# 9_-RELAYS.net
KiCad netlist of a schematic drawn in Altium Designer
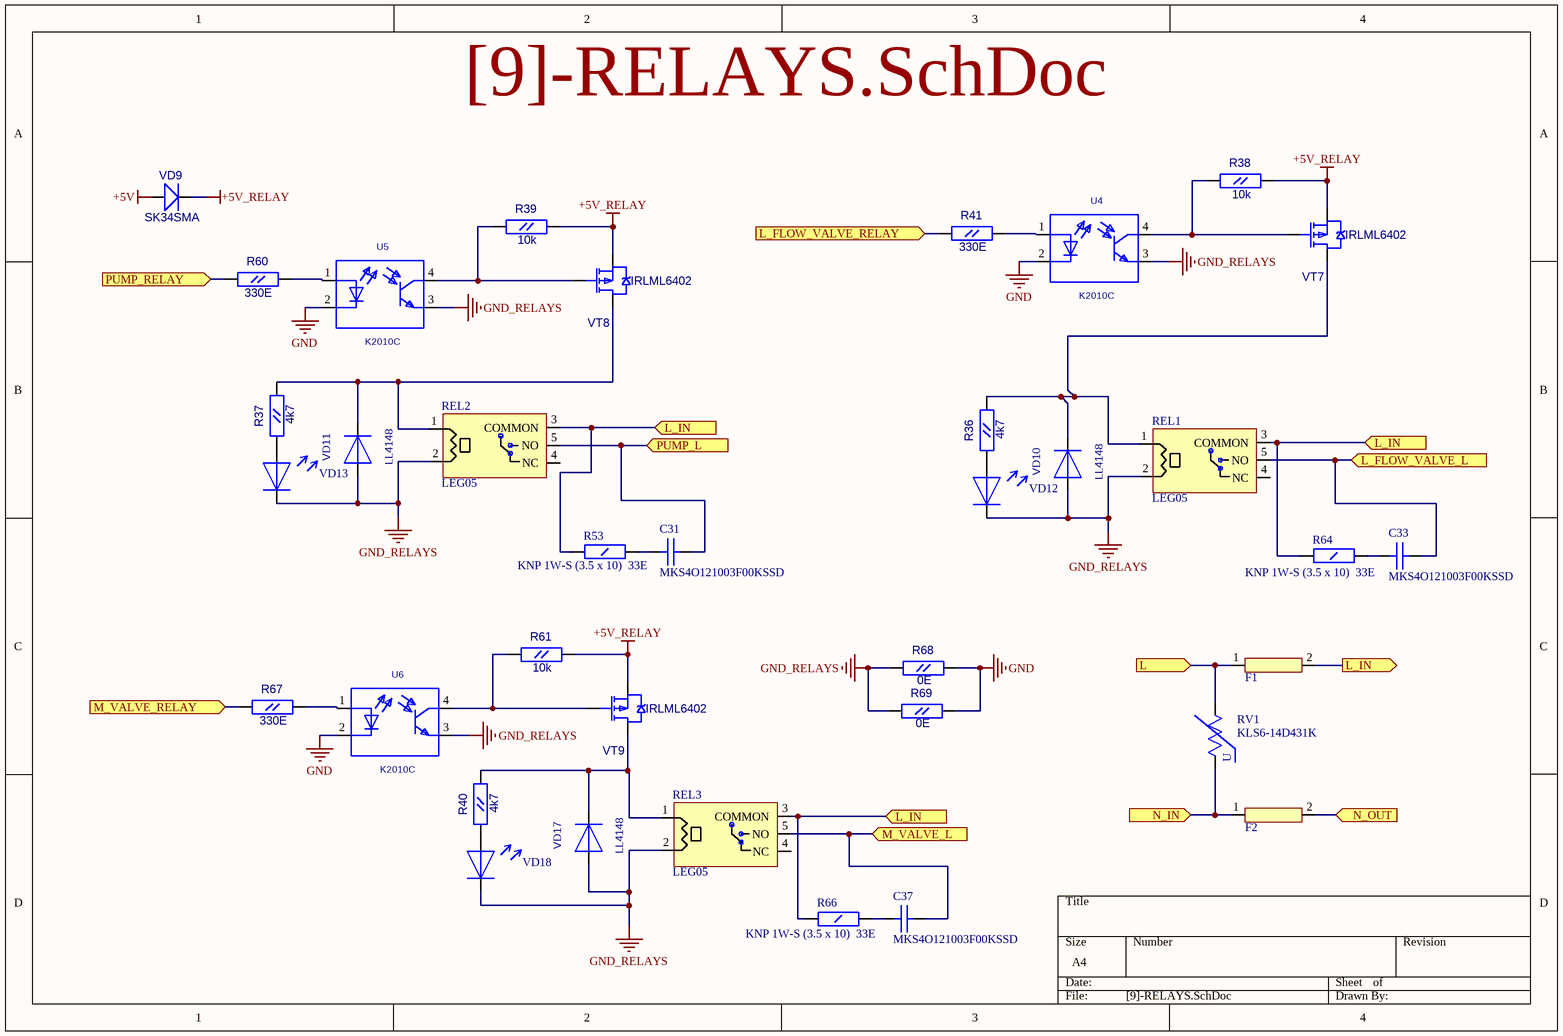
[diagram p0: [9]-RELAYS.SchDoc]

(export (version "E")
  (design (tool "Eeschema 10.0.6"))
  (components
    (comp (ref "C31")
      (value "MKS4O121003F00KSSD")
      (footprint "CAP_HV_13x5")
      (libsource (lib "fizik_lib") (part "CAP_HV_13x5"))
    )
    (comp (ref "C33")
      (value "MKS4O121003F00KSSD")
      (footprint "CAP_HV_13x5")
      (libsource (lib "fizik_lib") (part "CAP_HV_13x5"))
    )
    (comp (ref "C37")
      (value "MKS4O121003F00KSSD")
      (footprint "CAP_HV_13x5")
      (libsource (lib "fizik_lib") (part "CAP_HV_13x5"))
    )
    (comp (ref "F1")
      (value "KLS5-266(5x20)")
      (footprint "Fuse_5x20")
      (libsource (lib "fizik_lib") (part "Fuse KLS5-266(5x20)"))
    )
    (comp (ref "F2")
      (value "KLS5-266(5x20)")
      (footprint "Fuse_5x20")
      (libsource (lib "fizik_lib") (part "Fuse KLS5-266(5x20)"))
    )
    (comp (ref "R36")
      (value "4k7")
      (footprint "RC0603")
      (description "RC0603")
      (libsource (lib "fizik_lib") (part "RC0603"))
    )
    (comp (ref "R37")
      (value "4k7")
      (footprint "RC0603")
      (description "RC0603")
      (libsource (lib "fizik_lib") (part "RC0603"))
    )
    (comp (ref "R38")
      (value "10k")
      (footprint "RC0603")
      (description "RC0603")
      (libsource (lib "fizik_lib") (part "RC0603"))
    )
    (comp (ref "R39")
      (value "10k")
      (footprint "RC0603")
      (description "RC0603")
      (libsource (lib "fizik_lib") (part "RC0603"))
    )
    (comp (ref "R40")
      (value "4k7")
      (footprint "RC0603")
      (description "RC0603")
      (libsource (lib "fizik_lib") (part "RC0603"))
    )
    (comp (ref "R41")
      (value "330E")
      (footprint "RC0603")
      (description "RC0603")
      (libsource (lib "fizik_lib") (part "RC0603"))
    )
    (comp (ref "R53")
      (value "KNP 1W-S (3.5 x 10)  33E")
      (footprint "RES_10x4_THD")
      (description "THR resisto r10x3mm 0.5W")
      (libsource (lib "fizik_lib") (part "RC_1003_THR"))
    )
    (comp (ref "R60")
      (value "330E")
      (footprint "RC0603")
      (description "RC0603")
      (libsource (lib "fizik_lib") (part "RC0603"))
    )
    (comp (ref "R61")
      (value "10k")
      (footprint "RC0603")
      (description "RC0603")
      (libsource (lib "fizik_lib") (part "RC0603"))
    )
    (comp (ref "R64")
      (value "KNP 1W-S (3.5 x 10)  33E")
      (footprint "RES_10x4_THD")
      (description "THR resisto r10x3mm 0.5W")
      (libsource (lib "fizik_lib") (part "RC_1003_THR"))
    )
    (comp (ref "R66")
      (value "KNP 1W-S (3.5 x 10)  33E")
      (footprint "RES_10x4_THD")
      (description "THR resisto r10x3mm 0.5W")
      (libsource (lib "fizik_lib") (part "RC_1003_THR"))
    )
    (comp (ref "R67")
      (value "330E")
      (footprint "RC0603")
      (description "RC0603")
      (libsource (lib "fizik_lib") (part "RC0603"))
    )
    (comp (ref "R68")
      (value "0E")
      (footprint "RC0805")
      (description "RC0805")
      (libsource (lib "fizik_lib") (part "RC0805"))
    )
    (comp (ref "R69")
      (value "0E")
      (footprint "RC0805")
      (description "RC0805")
      (libsource (lib "fizik_lib") (part "RC0805"))
    )
    (comp (ref "REL1")
      (value "LEG05")
      (footprint "RELAY_SRD-05")
      (description "Relay 5V 70mA Songle")
      (libsource (lib "fizik_lib") (part "SRD-05VDC-SL-C"))
    )
    (comp (ref "REL2")
      (value "LEG05")
      (footprint "RELAY_SRD-05")
      (description "Relay 5V 70mA Songle")
      (libsource (lib "fizik_lib") (part "SRD-05VDC-SL-C"))
    )
    (comp (ref "REL3")
      (value "LEG05")
      (footprint "RELAY_SRD-05")
      (description "Relay 5V 70mA Songle")
      (libsource (lib "fizik_lib") (part "SRD-05VDC-SL-C"))
    )
    (comp (ref "RV1")
      (value "KLS6-14D431K")
      (footprint "Varistor_14MM")
      (description "Varistor diameter 14mm")
      (libsource (lib "fizik_lib") (part "KLS6-14D431K"))
    )
    (comp (ref "U4")
      (value "K2010C")
      (footprint "PC817")
      (description "K10102C")
      (libsource (lib "fizik_lib") (part "K10102C"))
    )
    (comp (ref "U5")
      (value "K2010C")
      (footprint "PC817")
      (description "K10102C")
      (libsource (lib "fizik_lib") (part "K10102C"))
    )
    (comp (ref "U6")
      (value "K2010C")
      (footprint "PC817")
      (description "K10102C")
      (libsource (lib "fizik_lib") (part "K10102C"))
    )
    (comp (ref "VD9")
      (value "SK34SMA")
      (footprint "SMA")
      (description "Schottky Rectifier")
      (libsource (lib "gprs_modem") (part "SK34SMA"))
    )
    (comp (ref "VD10") (value "LL4148") (footprint "SOD-80") (libsource (lib "fizik_lib") (part "LL4148")))
    (comp (ref "VD11") (value "LL4148") (footprint "SOD-80") (libsource (lib "fizik_lib") (part "LL4148")))
    (comp (ref "VD12")
      (value "LED_0805")
      (footprint "LED0805")
      (libsource (lib "fizik_lib") (part "LED_0805"))
    )
    (comp (ref "VD13")
      (value "LED_0805")
      (footprint "LED0805")
      (libsource (lib "fizik_lib") (part "LED_0805"))
    )
    (comp (ref "VD17") (value "LL4148") (footprint "SOD-80") (libsource (lib "fizik_lib") (part "LL4148")))
    (comp (ref "VD18")
      (value "LED_0805")
      (footprint "LED0805")
      (libsource (lib "fizik_lib") (part "LED_0805"))
    )
    (comp (ref "VT7")
      (value "IRLML6402")
      (footprint "SOT-23(123)")
      (description "HEXFET Power MOSFET")
      (libsource (lib "fizik_lib") (part "IRLML6402"))
    )
    (comp (ref "VT8")
      (value "IRLML6402")
      (footprint "SOT-23(123)")
      (description "HEXFET Power MOSFET")
      (libsource (lib "fizik_lib") (part "IRLML6402"))
    )
    (comp (ref "VT9")
      (value "IRLML6402")
      (footprint "SOT-23(123)")
      (description "HEXFET Power MOSFET")
      (libsource (lib "fizik_lib") (part "IRLML6402"))
    )
  )
  (nets
    (net (code "1") (name "+5V") (class "Default")
      (node (ref "VD9") (pin "1") (pinfunction "A_1") (pintype "passive"))
    )
    (net (code "2") (name "+5V_RELAY") (class "Default")
      (node (ref "R38") (pin "2") (pinfunction "B_2") (pintype "passive"))
      (node (ref "R39") (pin "2") (pinfunction "B_2") (pintype "passive"))
      (node (ref "R61") (pin "2") (pinfunction "B_2") (pintype "passive"))
      (node (ref "VD9") (pin "2") (pinfunction "K_2") (pintype "passive"))
      (node (ref "VT7") (pin "2") (pinfunction "S_2") (pintype "passive"))
      (node (ref "VT8") (pin "2") (pinfunction "S_2") (pintype "passive"))
      (node (ref "VT9") (pin "2") (pinfunction "S_2") (pintype "passive"))
    )
    (net (code "3") (name "/L") (class "Default")
      (node (ref "F1") (pin "1") (pinfunction "9_1") (pintype "passive"))
      (node (ref "RV1") (pin "2") (pinfunction "B_2") (pintype "passive"))
    )
    (net (code "4") (name "/L_FLOW_VALVE_L") (class "Default")
      (node (ref "C33") (pin "2") (pinfunction "B_2") (pintype "passive"))
      (node (ref "REL1") (pin "5") (pinfunction "NO_5") (pintype "passive"))
    )
    (net (code "5") (name "/L_FLOW_VALVE_RELAY") (class "Default")
      (node (ref "R41") (pin "1") (pinfunction "A_1") (pintype "passive"))
    )
    (net (code "6") (name "/L_IN") (class "Default")
      (node (ref "F1") (pin "2") (pinfunction "2_2") (pintype "passive"))
      (node (ref "R53") (pin "2") (pinfunction "B_2") (pintype "passive"))
      (node (ref "R64") (pin "2") (pinfunction "B_2") (pintype "passive"))
      (node (ref "R66") (pin "2") (pinfunction "B_2") (pintype "passive"))
      (node (ref "REL1") (pin "3") (pinfunction "COMMON_3") (pintype "passive"))
      (node (ref "REL2") (pin "3") (pinfunction "COMMON_3") (pintype "passive"))
      (node (ref "REL3") (pin "3") (pinfunction "COMMON_3") (pintype "passive"))
    )
    (net (code "7") (name "/M_VALVE_L") (class "Default")
      (node (ref "C37") (pin "2") (pinfunction "B_2") (pintype "passive"))
      (node (ref "REL3") (pin "5") (pinfunction "NO_5") (pintype "passive"))
    )
    (net (code "8") (name "/M_VALVE_RELAY") (class "Default")
      (node (ref "R67") (pin "1") (pinfunction "A_1") (pintype "passive"))
    )
    (net (code "9") (name "/N_IN") (class "Default")
      (node (ref "F2") (pin "1") (pinfunction "9_1") (pintype "passive"))
      (node (ref "RV1") (pin "1") (pinfunction "A_1") (pintype "passive"))
    )
    (net (code "10") (name "/N_OUT") (class "Default")
      (node (ref "F2") (pin "2") (pinfunction "2_2") (pintype "passive"))
    )
    (net (code "11") (name "/PUMP_L") (class "Default")
      (node (ref "C31") (pin "2") (pinfunction "B_2") (pintype "passive"))
      (node (ref "REL2") (pin "5") (pinfunction "NO_5") (pintype "passive"))
    )
    (net (code "12") (name "/PUMP_RELAY") (class "Default")
      (node (ref "R60") (pin "1") (pinfunction "A_1") (pintype "passive"))
    )
    (net (code "13") (name "GND") (class "Default")
      (node (ref "R68") (pin "2") (pinfunction "B_2") (pintype "passive"))
      (node (ref "R69") (pin "2") (pinfunction "B_2") (pintype "passive"))
      (node (ref "U4") (pin "2") (pintype "passive"))
      (node (ref "U5") (pin "2") (pintype "passive"))
      (node (ref "U6") (pin "2") (pintype "passive"))
    )
    (net (code "14") (name "GND_RELAYS") (class "Default")
      (node (ref "R68") (pin "1") (pinfunction "A_1") (pintype "passive"))
      (node (ref "R69") (pin "1") (pinfunction "A_1") (pintype "passive"))
      (node (ref "REL1") (pin "2") (pinfunction "53_2") (pintype "passive"))
      (node (ref "REL2") (pin "2") (pinfunction "53_2") (pintype "passive"))
      (node (ref "REL3") (pin "2") (pinfunction "53_2") (pintype "passive"))
      (node (ref "U4") (pin "3") (pintype "passive"))
      (node (ref "U5") (pin "3") (pintype "passive"))
      (node (ref "U6") (pin "3") (pintype "passive"))
      (node (ref "VD10") (pin "1") (pinfunction "-_1") (pintype "passive"))
      (node (ref "VD11") (pin "1") (pinfunction "-_1") (pintype "passive"))
      (node (ref "VD12") (pin "2") (pintype "passive"))
      (node (ref "VD13") (pin "2") (pintype "passive"))
      (node (ref "VD17") (pin "1") (pinfunction "-_1") (pintype "passive"))
      (node (ref "VD18") (pin "2") (pintype "passive"))
    )
    (net (code "15") (name "Net-(C31-A)") (class "Default")
      (node (ref "C31") (pin "1") (pinfunction "A_1") (pintype "passive"))
      (node (ref "R53") (pin "1") (pinfunction "A_1") (pintype "passive"))
    )
    (net (code "16") (name "Net-(C33-A)") (class "Default")
      (node (ref "C33") (pin "1") (pinfunction "A_1") (pintype "passive"))
      (node (ref "R64") (pin "1") (pinfunction "A_1") (pintype "passive"))
    )
    (net (code "17") (name "Net-(C37-A)") (class "Default")
      (node (ref "C37") (pin "1") (pinfunction "A_1") (pintype "passive"))
      (node (ref "R66") (pin "1") (pinfunction "A_1") (pintype "passive"))
    )
    (net (code "18") (name "Net-(R36-A)") (class "Default")
      (node (ref "R36") (pin "1") (pinfunction "A_1") (pintype "passive"))
      (node (ref "VD12") (pin "1") (pintype "passive"))
    )
    (net (code "19") (name "Net-(R36-B)") (class "Default")
      (node (ref "R36") (pin "2") (pinfunction "B_2") (pintype "passive"))
      (node (ref "REL1") (pin "1") (pinfunction "52_1") (pintype "passive"))
      (node (ref "VD10") (pin "2") (pinfunction "+_2") (pintype "passive"))
      (node (ref "VT7") (pin "3") (pinfunction "D_3") (pintype "passive"))
    )
    (net (code "20") (name "Net-(R37-A)") (class "Default")
      (node (ref "R37") (pin "1") (pinfunction "A_1") (pintype "passive"))
      (node (ref "VD13") (pin "1") (pintype "passive"))
    )
    (net (code "21") (name "Net-(R37-B)") (class "Default")
      (node (ref "R37") (pin "2") (pinfunction "B_2") (pintype "passive"))
      (node (ref "REL2") (pin "1") (pinfunction "52_1") (pintype "passive"))
      (node (ref "VD11") (pin "2") (pinfunction "+_2") (pintype "passive"))
      (node (ref "VT8") (pin "3") (pinfunction "D_3") (pintype "passive"))
    )
    (net (code "22") (name "Net-(R38-A)") (class "Default")
      (node (ref "R38") (pin "1") (pinfunction "A_1") (pintype "passive"))
      (node (ref "U4") (pin "4") (pintype "passive"))
      (node (ref "VT7") (pin "1") (pinfunction "G_1") (pintype "passive"))
    )
    (net (code "23") (name "Net-(R39-A)") (class "Default")
      (node (ref "R39") (pin "1") (pinfunction "A_1") (pintype "passive"))
      (node (ref "U5") (pin "4") (pintype "passive"))
      (node (ref "VT8") (pin "1") (pinfunction "G_1") (pintype "passive"))
    )
    (net (code "24") (name "Net-(R40-A)") (class "Default")
      (node (ref "R40") (pin "1") (pinfunction "A_1") (pintype "passive"))
      (node (ref "VD18") (pin "1") (pintype "passive"))
    )
    (net (code "25") (name "Net-(R40-B)") (class "Default")
      (node (ref "R40") (pin "2") (pinfunction "B_2") (pintype "passive"))
      (node (ref "REL3") (pin "1") (pinfunction "52_1") (pintype "passive"))
      (node (ref "VD17") (pin "2") (pinfunction "+_2") (pintype "passive"))
      (node (ref "VT9") (pin "3") (pinfunction "D_3") (pintype "passive"))
    )
    (net (code "26") (name "Net-(R41-B)") (class "Default")
      (node (ref "R41") (pin "2") (pinfunction "B_2") (pintype "passive"))
      (node (ref "U4") (pin "1") (pintype "passive"))
    )
    (net (code "27") (name "Net-(R60-B)") (class "Default")
      (node (ref "R60") (pin "2") (pinfunction "B_2") (pintype "passive"))
      (node (ref "U5") (pin "1") (pintype "passive"))
    )
    (net (code "28") (name "Net-(R61-A)") (class "Default")
      (node (ref "R61") (pin "1") (pinfunction "A_1") (pintype "passive"))
      (node (ref "U6") (pin "4") (pintype "passive"))
      (node (ref "VT9") (pin "1") (pinfunction "G_1") (pintype "passive"))
    )
    (net (code "29") (name "Net-(R67-B)") (class "Default")
      (node (ref "R67") (pin "2") (pinfunction "B_2") (pintype "passive"))
      (node (ref "U6") (pin "1") (pintype "passive"))
    )
    (net (code "30") (name "unconnected-(REL1-NC-Pad4)") (class "Default")
      (node (ref "REL1") (pin "4") (pinfunction "NC_4") (pintype "passive"))
    )
    (net (code "31") (name "unconnected-(REL2-NC-Pad4)") (class "Default")
      (node (ref "REL2") (pin "4") (pinfunction "NC_4") (pintype "passive"))
    )
    (net (code "32") (name "unconnected-(REL3-NC-Pad4)") (class "Default")
      (node (ref "REL3") (pin "4") (pinfunction "NC_4") (pintype "passive"))
    )
  )
)
